# CPU.net
KiCad netlist of a schematic drawn in Altium Designer
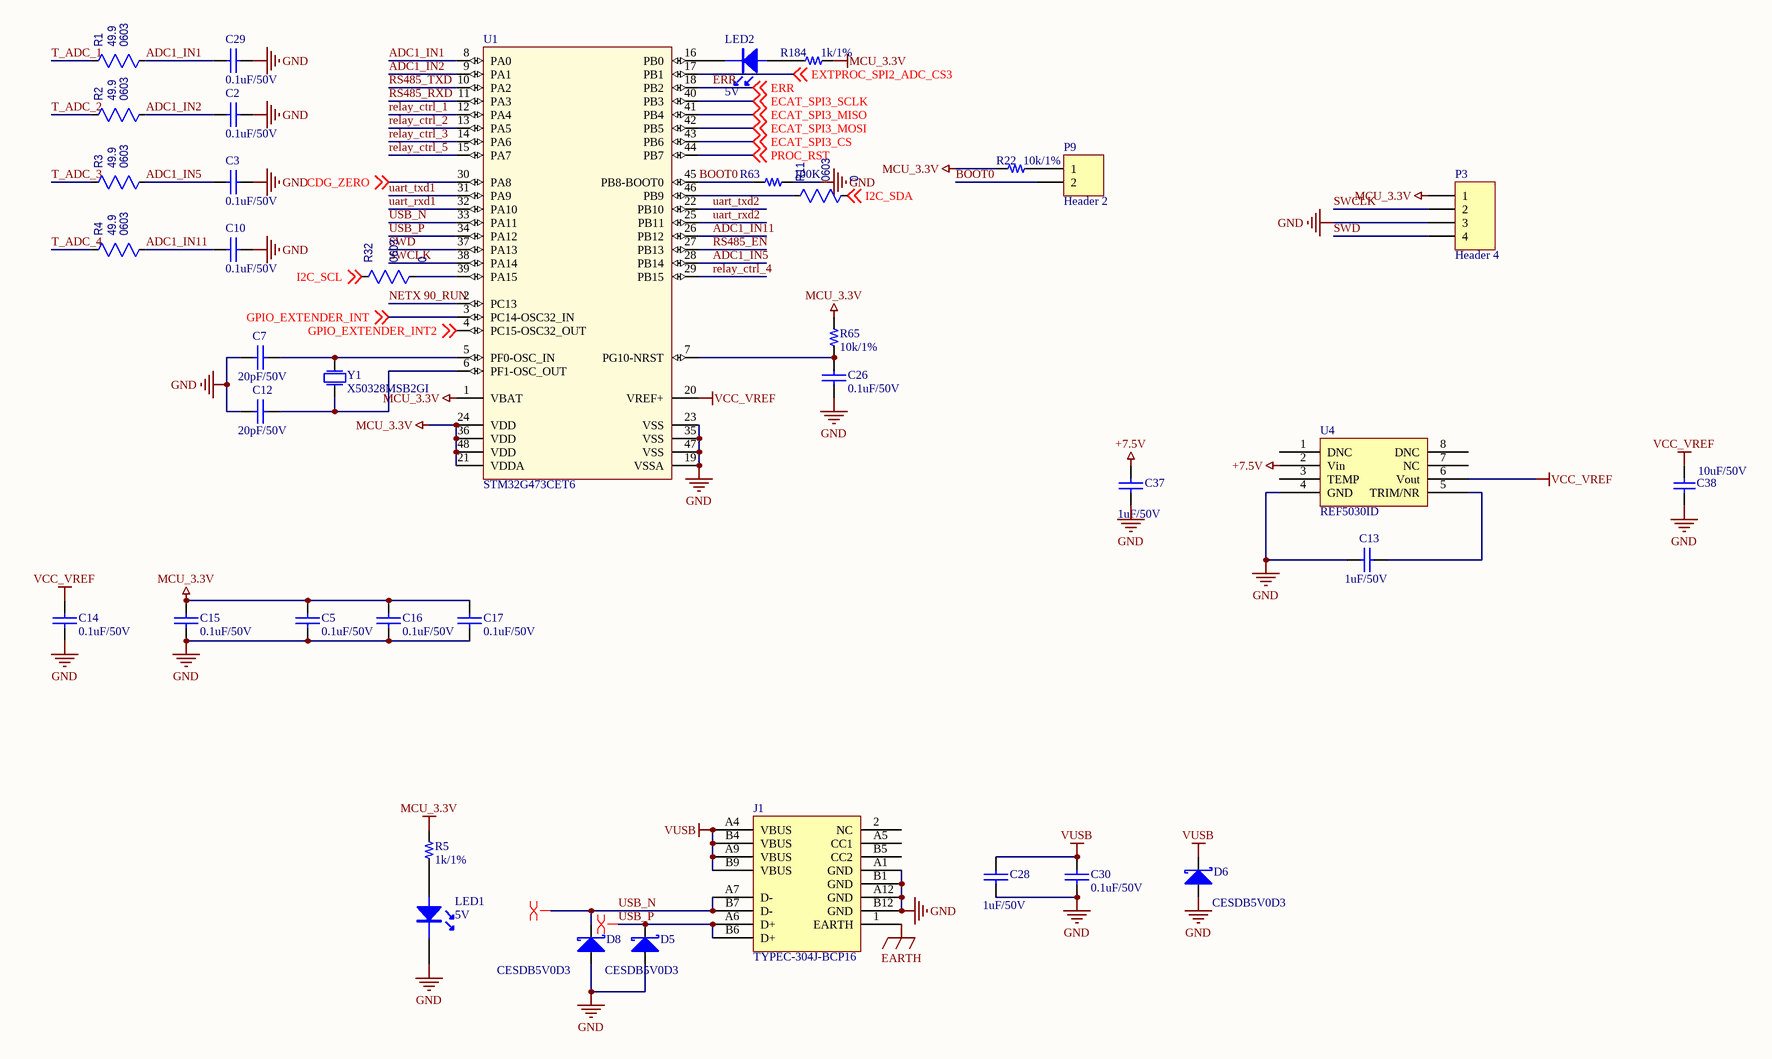
[diagram p0: CPU.SchDoc]

(export (version "E")
  (design (tool "Eeschema 10.0.6"))
  (components
    (comp (ref "C2")
      (value "0.1uF/50V")
      (footprint "CAPC1608X092N_0603")
      (fields (field (name "PARTNUMBER") "CC0603KRX7R9BB104"))
      (libsource (lib "SM") (part "CAP"))
    )
    (comp (ref "C3")
      (value "0.1uF/50V")
      (footprint "CAPC1608X092N_0603")
      (fields (field (name "PARTNUMBER") "CC0603KRX7R9BB104"))
      (libsource (lib "SM") (part "CAP"))
    )
    (comp (ref "C5")
      (value "0.1uF/50V")
      (footprint "CAPC1608X092N_0603")
      (fields (field (name "PARTNUMBER") "CC0603KRX7R9BB104"))
      (libsource (lib "SM") (part "CAP"))
    )
    (comp (ref "C7")
      (value "20pF/50V")
      (footprint "CAPC1608X092N_0603")
      (fields (field (name "PARTNUMBER") "CC0603JRNPO9BN200") (field (name "Comment") "20pF/25V"))
      (libsource (lib "SM") (part "CAP"))
    )
    (comp (ref "C10")
      (value "0.1uF/50V")
      (footprint "CAPC1608X092N_0603")
      (fields (field (name "PARTNUMBER") "CC0603KRX7R9BB104"))
      (libsource (lib "SM") (part "CAP"))
    )
    (comp (ref "C12")
      (value "20pF/50V")
      (footprint "CAPC1608X092N_0603")
      (fields (field (name "PARTNUMBER") "CC0603JRNPO9BN200") (field (name "Comment") "20pF/25V"))
      (libsource (lib "SM") (part "CAP"))
    )
    (comp (ref "C13")
      (value "1uF/50V")
      (footprint "CAPC1608X092N_0603")
      (fields (field (name "PARTNUMBER") "CL10A105KB8NNNC"))
      (libsource (lib "SM") (part "CAP"))
    )
    (comp (ref "C14")
      (value "0.1uF/50V")
      (footprint "CAPC1608X092N_0603")
      (fields (field (name "PARTNUMBER") "CC0603KRX7R9BB104"))
      (libsource (lib "SM") (part "CAP"))
    )
    (comp (ref "C15")
      (value "0.1uF/50V")
      (footprint "CAPC1608X092N_0603")
      (fields (field (name "PARTNUMBER") "CC0603KRX7R9BB104"))
      (libsource (lib "SM") (part "CAP"))
    )
    (comp (ref "C16")
      (value "0.1uF/50V")
      (footprint "CAPC1608X092N_0603")
      (fields (field (name "PARTNUMBER") "CC0603KRX7R9BB104"))
      (libsource (lib "SM") (part "CAP"))
    )
    (comp (ref "C17")
      (value "0.1uF/50V")
      (footprint "CAPC1608X092N_0603")
      (fields (field (name "PARTNUMBER") "CC0603KRX7R9BB104"))
      (libsource (lib "SM") (part "CAP"))
    )
    (comp (ref "C26")
      (value "0.1uF/50V")
      (footprint "CAPC1608X092N_0603")
      (fields (field (name "PARTNUMBER") "CC0603KRX7R9BB104"))
      (libsource (lib "SM") (part "CAP"))
    )
    (comp (ref "C28")
      (value "1uF/50V")
      (footprint "CAPC1608X092N_0603")
      (fields (field (name "PARTNUMBER") "CL10A105KB8NNNC"))
      (libsource (lib "SM") (part "CAP"))
    )
    (comp (ref "C29")
      (value "0.1uF/50V")
      (footprint "CAPC1608X092N_0603")
      (fields (field (name "PARTNUMBER") "CC0603KRX7R9BB104"))
      (libsource (lib "SM") (part "CAP"))
    )
    (comp (ref "C30")
      (value "0.1uF/50V")
      (footprint "CAPC1608X092N_0603")
      (fields (field (name "PARTNUMBER") "CC0603KRX7R9BB104"))
      (libsource (lib "SM") (part "CAP"))
    )
    (comp (ref "C37")
      (value "1uF/50V")
      (footprint "CAPC1608X092N_0603")
      (fields (field (name "PARTNUMBER") "CL10A105KB8NNNC"))
      (libsource (lib "SM") (part "CAP"))
    )
    (comp (ref "C38")
      (value "10uF/50V")
      (footprint "CAPC2012X127N_0805")
      (fields (field (name "PARTNUMBER") "CL21A106KBYQNNE") (field (name "PUBLISHER") "Altium Limited"))
      (libsource (lib "Miscellaneous Devices") (part "Cap"))
    )
    (comp (ref "D5") (value "CESDB5V0D3") (footprint "SOD323") (libsource (lib "*") (part "DIODE S")))
    (comp (ref "D6") (value "CESDB5V0D3") (footprint "SOD323") (libsource (lib "*") (part "DIODE S")))
    (comp (ref "D8") (value "CESDB5V0D3") (footprint "SOD323") (libsource (lib "*") (part "DIODE S")))
    (comp (ref "J1")
      (value "TYPEC-304J-BCP16")
      (footprint "TYPEC_16P")
      (libsource (lib "Schlib_20110825") (part "TYPE C_16P"))
    )
    (comp (ref "LED1") (value "5V") (footprint "0603LED") (libsource (lib "*") (part "LED")))
    (comp (ref "LED2") (value "5V") (footprint "0603LED") (libsource (lib "*") (part "LED")))
    (comp (ref "P3")
      (value "Header 4")
      (footprint "HDR1X4")
      (fields (field (name "PARTNUMBER") "PZ254V-11-04P") (field (name "PUBLISHER") "Altium Limited"))
      (libsource (lib "Miscellaneous Connectors") (part "Header 4"))
    )
    (comp (ref "P9")
      (value "Header 2")
      (footprint "HDR1X2")
      (fields (field (name "PARTNUMBER") "PZ254V-11-02P") (field (name "PUBLISHER") "Altium Limited"))
      (libsource (lib "Miscellaneous Connectors") (part "Header 2"))
    )
    (comp (ref "R1")
      (value "49.9")
      (footprint "RESC1608X055N_0603")
      (fields
        (field (name "PARTNUMBER") "RC0603FR-0749R9L")
        (field (name "TOLERANCE") "tol")
        (field (name "PACKAGE") "0603")
      )
      (libsource (lib "Karl") (part "Resistor_0603"))
    )
    (comp (ref "R2")
      (value "49.9")
      (footprint "RESC1608X055N_0603")
      (fields
        (field (name "PARTNUMBER") "RC0603FR-0749R9L")
        (field (name "TOLERANCE") "tol")
        (field (name "PACKAGE") "0603")
      )
      (libsource (lib "Karl") (part "Resistor_0603"))
    )
    (comp (ref "R3")
      (value "49.9")
      (footprint "RESC1608X055N_0603")
      (fields
        (field (name "PARTNUMBER") "RC0603FR-0749R9L")
        (field (name "TOLERANCE") "tol")
        (field (name "PACKAGE") "0603")
      )
      (libsource (lib "Karl") (part "Resistor_0603"))
    )
    (comp (ref "R4")
      (value "49.9")
      (footprint "RESC1608X055N_0603")
      (fields
        (field (name "PARTNUMBER") "RC0603FR-0749R9L")
        (field (name "TOLERANCE") "tol")
        (field (name "PACKAGE") "0603")
      )
      (libsource (lib "Karl") (part "Resistor_0603"))
    )
    (comp (ref "R5")
      (value "1k/1%")
      (footprint "RESC1608X055N_0603")
      (fields (field (name "PARTNUMBER") "RC0603FR-071KL"))
      (libsource (lib "JRJ_1") (part "R"))
    )
    (comp (ref "R11")
      (value "0")
      (footprint "RESC1608X055N_0603")
      (fields
        (field (name "PARTNUMBER") "RC0603JR-070RL")
        (field (name "TOLERANCE") "tol")
        (field (name "PACKAGE") "0603")
      )
      (libsource (lib "Karl") (part "Resistor_0603"))
    )
    (comp (ref "R22")
      (value "10k/1%")
      (footprint "RESC1608X055N_0603")
      (fields (field (name "PARTNUMBER") "RC0603FR-0710KL"))
      (libsource (lib "JRJ_1") (part "R"))
    )
    (comp (ref "R32")
      (value "0")
      (footprint "RESC1608X055N_0603")
      (fields
        (field (name "PARTNUMBER") "RC0603JR-070RL")
        (field (name "TOLERANCE") "tol")
        (field (name "PACKAGE") "0603")
      )
      (libsource (lib "Karl") (part "Resistor_0603"))
    )
    (comp (ref "R63")
      (value "100K")
      (footprint "RESC1608X055N_0603")
      (fields (field (name "PARTNUMBER") "RC0603FR-07100KL"))
      (libsource (lib "JRJ_1") (part "R"))
    )
    (comp (ref "R65")
      (value "10k/1%")
      (footprint "RESC1608X055N_0603")
      (fields (field (name "PARTNUMBER") "RC0603FR-0710KL"))
      (libsource (lib "JRJ_1") (part "R"))
    )
    (comp (ref "R184")
      (value "1k/1%")
      (footprint "RESC1608X055N_0603")
      (fields (field (name "PARTNUMBER") "RC0603FR-071KL"))
      (libsource (lib "JRJ_1") (part "R"))
    )
    (comp (ref "U1")
      (value "STM32G473CET6")
      (footprint "Bogen:STM-LQFP48_N")
      (libsource (lib "Bogen") (part "STM32G473CET6"))
    )
    (comp (ref "U4")
      (value "REF5030ID")
      (footprint "SO-8")
      (fields (field (name "PARTNUMBER") "REF5030IDR"))
      (libsource (lib "Schlib1") (part "REF5030"))
    )
    (comp (ref "Y1")
      (value "X50328MSB2GI")
      (footprint "CRAY_5032")
      (libsource (lib "Miscellaneous Devices") (part "XTAL"))
    )
  )
  (nets
    (net (code "1") (name "+7.5V") (class "Default")
      (node (ref "C37") (pin "2") (pinfunction "2_2") (pintype "passive"))
      (node (ref "U4") (pin "2") (pinfunction "Vin_2") (pintype "passive"))
    )
    (net (code "2") (name "/ADC1_IN1") (class "Default")
      (node (ref "C29") (pin "2") (pinfunction "2_2") (pintype "passive"))
      (node (ref "R1") (pin "1") (pinfunction "1_1") (pintype "passive"))
      (node (ref "U1") (pin "8") (pinfunction "PA0_8") (pintype "bidirectional"))
    )
    (net (code "3") (name "/ADC1_IN2") (class "Default")
      (node (ref "C2") (pin "2") (pinfunction "2_2") (pintype "passive"))
      (node (ref "R2") (pin "1") (pinfunction "1_1") (pintype "passive"))
      (node (ref "U1") (pin "9") (pinfunction "PA1_9") (pintype "bidirectional"))
    )
    (net (code "4") (name "/ADC1_IN5") (class "Default")
      (node (ref "C3") (pin "2") (pinfunction "2_2") (pintype "passive"))
      (node (ref "R3") (pin "1") (pinfunction "1_1") (pintype "passive"))
      (node (ref "U1") (pin "28") (pinfunction "PB14_28") (pintype "bidirectional"))
    )
    (net (code "5") (name "/ADC1_IN11") (class "Default")
      (node (ref "C10") (pin "2") (pinfunction "2_2") (pintype "passive"))
      (node (ref "R4") (pin "1") (pinfunction "1_1") (pintype "passive"))
      (node (ref "U1") (pin "26") (pinfunction "PB12_26") (pintype "bidirectional"))
    )
    (net (code "6") (name "/BOOT0") (class "Default")
      (node (ref "P9") (pin "2") (pinfunction "2_2") (pintype "passive"))
      (node (ref "R63") (pin "1") (pintype "passive"))
      (node (ref "U1") (pin "45") (pinfunction "PB8-BOOT0_45") (pintype "bidirectional"))
    )
    (net (code "7") (name "/NETX 90_RUN") (class "Default")
      (node (ref "U1") (pin "2") (pinfunction "PC13_2") (pintype "bidirectional"))
    )
    (net (code "8") (name "/RS485_EN") (class "Default")
      (node (ref "U1") (pin "27") (pinfunction "PB13_27") (pintype "bidirectional"))
    )
    (net (code "9") (name "/RS485_RXD") (class "Default")
      (node (ref "U1") (pin "11") (pinfunction "PA3_11") (pintype "bidirectional"))
    )
    (net (code "10") (name "/RS485_TXD") (class "Default")
      (node (ref "U1") (pin "10") (pinfunction "PA2_10") (pintype "bidirectional"))
    )
    (net (code "11") (name "/SWCLK") (class "Default")
      (node (ref "P3") (pin "2") (pinfunction "2_2") (pintype "passive"))
      (node (ref "U1") (pin "38") (pinfunction "PA14_38") (pintype "bidirectional"))
    )
    (net (code "12") (name "/SWD") (class "Default")
      (node (ref "P3") (pin "4") (pinfunction "4_4") (pintype "passive"))
      (node (ref "U1") (pin "37") (pinfunction "PA13_37") (pintype "bidirectional"))
    )
    (net (code "13") (name "/T_ADC_1") (class "Default")
      (node (ref "R1") (pin "2") (pinfunction "2_2") (pintype "passive"))
    )
    (net (code "14") (name "/T_ADC_2") (class "Default")
      (node (ref "R2") (pin "2") (pinfunction "2_2") (pintype "passive"))
    )
    (net (code "15") (name "/T_ADC_3") (class "Default")
      (node (ref "R3") (pin "2") (pinfunction "2_2") (pintype "passive"))
    )
    (net (code "16") (name "/T_ADC_4") (class "Default")
      (node (ref "R4") (pin "2") (pinfunction "2_2") (pintype "passive"))
    )
    (net (code "17") (name "/USB_N") (class "Default")
      (node (ref "D8") (pin "2") (pinfunction "K_2") (pintype "passive"))
      (node (ref "J1") (pin "A7") (pinfunction "D-_A7") (pintype "passive"))
      (node (ref "J1") (pin "B7") (pinfunction "D-_B7") (pintype "passive"))
      (node (ref "U1") (pin "33") (pinfunction "PA11_33") (pintype "bidirectional"))
    )
    (net (code "18") (name "/USB_P") (class "Default")
      (node (ref "D5") (pin "2") (pinfunction "K_2") (pintype "passive"))
      (node (ref "J1") (pin "A6") (pinfunction "D+_A6") (pintype "passive"))
      (node (ref "J1") (pin "B6") (pinfunction "D+_B6") (pintype "passive"))
      (node (ref "U1") (pin "34") (pinfunction "PA12_34") (pintype "bidirectional"))
    )
    (net (code "19") (name "/relay_ctrl_1") (class "Default")
      (node (ref "U1") (pin "12") (pinfunction "PA4_12") (pintype "bidirectional"))
    )
    (net (code "20") (name "/relay_ctrl_2") (class "Default")
      (node (ref "U1") (pin "13") (pinfunction "PA5_13") (pintype "bidirectional"))
    )
    (net (code "21") (name "/relay_ctrl_3") (class "Default")
      (node (ref "U1") (pin "14") (pinfunction "PA6_14") (pintype "bidirectional"))
    )
    (net (code "22") (name "/relay_ctrl_4") (class "Default")
      (node (ref "U1") (pin "29") (pinfunction "PB15_29") (pintype "bidirectional"))
    )
    (net (code "23") (name "/relay_ctrl_5") (class "Default")
      (node (ref "U1") (pin "15") (pinfunction "PA7_15") (pintype "bidirectional"))
    )
    (net (code "24") (name "/uart_rxd1") (class "Default")
      (node (ref "U1") (pin "32") (pinfunction "PA10_32") (pintype "bidirectional"))
    )
    (net (code "25") (name "/uart_rxd2") (class "Default")
      (node (ref "U1") (pin "25") (pinfunction "PB11_25") (pintype "bidirectional"))
    )
    (net (code "26") (name "/uart_txd1") (class "Default")
      (node (ref "U1") (pin "31") (pinfunction "PA9_31") (pintype "bidirectional"))
    )
    (net (code "27") (name "/uart_txd2") (class "Default")
      (node (ref "U1") (pin "22") (pinfunction "PB10_22") (pintype "bidirectional"))
    )
    (net (code "28") (name "CDG_ZERO") (class "Default")
      (node (ref "U1") (pin "30") (pinfunction "PA8_30") (pintype "bidirectional"))
    )
    (net (code "29") (name "EARTH") (class "Default")
      (node (ref "J1") (pin "1") (pinfunction "EARTH_1") (pintype "passive"))
    )
    (net (code "30") (name "ECAT_SPI3_CS") (class "Default")
      (node (ref "U1") (pin "43") (pinfunction "PB6_43") (pintype "bidirectional"))
    )
    (net (code "31") (name "ECAT_SPI3_MISO") (class "Default")
      (node (ref "U1") (pin "41") (pinfunction "PB4_41") (pintype "bidirectional"))
    )
    (net (code "32") (name "ECAT_SPI3_MOSI") (class "Default")
      (node (ref "U1") (pin "42") (pinfunction "PB5_42") (pintype "bidirectional"))
    )
    (net (code "33") (name "ECAT_SPI3_SCLK") (class "Default")
      (node (ref "U1") (pin "40") (pinfunction "PB3_40") (pintype "bidirectional"))
    )
    (net (code "34") (name "ERR") (class "Default")
      (node (ref "U1") (pin "18") (pinfunction "PB2_18") (pintype "bidirectional"))
    )
    (net (code "35") (name "EXTPROC_SPI2_ADC_CS3") (class "Default")
      (node (ref "U1") (pin "17") (pinfunction "PB1_17") (pintype "bidirectional"))
    )
    (net (code "36") (name "GND") (class "Default")
      (node (ref "C10") (pin "1") (pinfunction "1_1") (pintype "passive"))
      (node (ref "C12") (pin "2") (pinfunction "2_2") (pintype "passive"))
      (node (ref "C13") (pin "2") (pinfunction "2_2") (pintype "passive"))
      (node (ref "C14") (pin "1") (pinfunction "1_1") (pintype "passive"))
      (node (ref "C15") (pin "1") (pinfunction "1_1") (pintype "passive"))
      (node (ref "C16") (pin "1") (pinfunction "1_1") (pintype "passive"))
      (node (ref "C17") (pin "1") (pinfunction "1_1") (pintype "passive"))
      (node (ref "C2") (pin "1") (pinfunction "1_1") (pintype "passive"))
      (node (ref "C26") (pin "1") (pinfunction "1_1") (pintype "passive"))
      (node (ref "C28") (pin "1") (pinfunction "1_1") (pintype "passive"))
      (node (ref "C29") (pin "1") (pinfunction "1_1") (pintype "passive"))
      (node (ref "C3") (pin "1") (pinfunction "1_1") (pintype "passive"))
      (node (ref "C30") (pin "1") (pinfunction "1_1") (pintype "passive"))
      (node (ref "C37") (pin "1") (pinfunction "1_1") (pintype "passive"))
      (node (ref "C38") (pin "1") (pinfunction "1_1") (pintype "passive"))
      (node (ref "C5") (pin "1") (pinfunction "1_1") (pintype "passive"))
      (node (ref "C7") (pin "2") (pinfunction "2_2") (pintype "passive"))
      (node (ref "D5") (pin "1") (pinfunction "A_1") (pintype "passive"))
      (node (ref "D6") (pin "1") (pinfunction "A_1") (pintype "passive"))
      (node (ref "D8") (pin "1") (pinfunction "A_1") (pintype "passive"))
      (node (ref "J1") (pin "A1") (pinfunction "GND_A1") (pintype "passive"))
      (node (ref "J1") (pin "A12") (pinfunction "GND_A12") (pintype "passive"))
      (node (ref "J1") (pin "B1") (pinfunction "GND_B1") (pintype "passive"))
      (node (ref "J1") (pin "B12") (pinfunction "GND_B12") (pintype "passive"))
      (node (ref "LED1") (pin "2") (pinfunction "2_2") (pintype "passive"))
      (node (ref "P3") (pin "3") (pinfunction "3_3") (pintype "passive"))
      (node (ref "R63") (pin "2") (pintype "passive"))
      (node (ref "U1") (pin "19") (pinfunction "VSSA_19") (pintype "power_in"))
      (node (ref "U1") (pin "23") (pinfunction "VSS_23") (pintype "power_in"))
      (node (ref "U1") (pin "35") (pinfunction "VSS_35") (pintype "power_in"))
      (node (ref "U1") (pin "47") (pinfunction "VSS_47") (pintype "power_in"))
      (node (ref "U4") (pin "4") (pinfunction "GND_4") (pintype "passive"))
    )
    (net (code "37") (name "GPIO_EXTENDER_INT") (class "Default")
      (node (ref "U1") (pin "3") (pinfunction "PC14-OSC32_IN_3") (pintype "bidirectional"))
    )
    (net (code "38") (name "GPIO_EXTENDER_INT2") (class "Default")
      (node (ref "U1") (pin "4") (pinfunction "PC15-OSC32_OUT_4") (pintype "bidirectional"))
    )
    (net (code "39") (name "I2C_SCL") (class "Default")
      (node (ref "R32") (pin "2") (pinfunction "2_2") (pintype "passive"))
    )
    (net (code "40") (name "I2C_SDA") (class "Default")
      (node (ref "R11") (pin "1") (pinfunction "1_1") (pintype "passive"))
    )
    (net (code "41") (name "MCU_3.3V") (class "Default")
      (node (ref "C15") (pin "2") (pinfunction "2_2") (pintype "passive"))
      (node (ref "C16") (pin "2") (pinfunction "2_2") (pintype "passive"))
      (node (ref "C17") (pin "2") (pinfunction "2_2") (pintype "passive"))
      (node (ref "C5") (pin "2") (pinfunction "2_2") (pintype "passive"))
      (node (ref "P3") (pin "1") (pinfunction "1_1") (pintype "passive"))
      (node (ref "R184") (pin "2") (pintype "passive"))
      (node (ref "R22") (pin "1") (pintype "passive"))
      (node (ref "R5") (pin "2") (pintype "passive"))
      (node (ref "R65") (pin "1") (pintype "passive"))
      (node (ref "U1") (pin "1") (pinfunction "VBAT_1") (pintype "power_in"))
      (node (ref "U1") (pin "21") (pinfunction "VDDA_21") (pintype "power_in"))
      (node (ref "U1") (pin "24") (pinfunction "VDD_24") (pintype "power_in"))
      (node (ref "U1") (pin "36") (pinfunction "VDD_36") (pintype "power_in"))
      (node (ref "U1") (pin "48") (pinfunction "VDD_48") (pintype "power_in"))
    )
    (net (code "42") (name "Net-(LED1-Pad1)") (class "Default")
      (node (ref "LED1") (pin "1") (pinfunction "1_1") (pintype "passive"))
      (node (ref "R5") (pin "1") (pintype "passive"))
    )
    (net (code "43") (name "Net-(LED2-Pad1)") (class "Default")
      (node (ref "LED2") (pin "1") (pinfunction "1_1") (pintype "passive"))
      (node (ref "R184") (pin "1") (pintype "passive"))
    )
    (net (code "44") (name "Net-(P9-Pad1)") (class "Default")
      (node (ref "P9") (pin "1") (pinfunction "1_1") (pintype "passive"))
      (node (ref "R22") (pin "2") (pintype "passive"))
    )
    (net (code "45") (name "Net-(U1-PA15)") (class "Default")
      (node (ref "R32") (pin "1") (pinfunction "1_1") (pintype "passive"))
      (node (ref "U1") (pin "39") (pinfunction "PA15_39") (pintype "bidirectional"))
    )
    (net (code "46") (name "Net-(U1-PB0)") (class "Default")
      (node (ref "LED2") (pin "2") (pinfunction "2_2") (pintype "passive"))
      (node (ref "U1") (pin "16") (pinfunction "PB0_16") (pintype "bidirectional"))
    )
    (net (code "47") (name "Net-(U1-PB9)") (class "Default")
      (node (ref "R11") (pin "2") (pinfunction "2_2") (pintype "passive"))
      (node (ref "U1") (pin "46") (pinfunction "PB9_46") (pintype "bidirectional"))
    )
    (net (code "48") (name "Net-(U1-PF0-OSC_IN)") (class "Default")
      (node (ref "C7") (pin "1") (pinfunction "1_1") (pintype "passive"))
      (node (ref "U1") (pin "5") (pinfunction "PF0-OSC_IN_5") (pintype "bidirectional"))
      (node (ref "Y1") (pin "1") (pinfunction "P1_1") (pintype "passive"))
    )
    (net (code "49") (name "Net-(U1-PF1-OSC_OUT)") (class "Default")
      (node (ref "C12") (pin "1") (pinfunction "1_1") (pintype "passive"))
      (node (ref "U1") (pin "6") (pinfunction "PF1-OSC_OUT_6") (pintype "bidirectional"))
      (node (ref "Y1") (pin "2") (pinfunction "P2_2") (pintype "passive"))
    )
    (net (code "50") (name "Net-(U1-PG10-NRST)") (class "Default")
      (node (ref "C26") (pin "2") (pinfunction "2_2") (pintype "passive"))
      (node (ref "R65") (pin "2") (pintype "passive"))
      (node (ref "U1") (pin "7") (pinfunction "PG10-NRST_7") (pintype "bidirectional"))
    )
    (net (code "51") (name "Net-(U4-TRIM{slash}NR)") (class "Default")
      (node (ref "C13") (pin "1") (pinfunction "1_1") (pintype "passive"))
      (node (ref "U4") (pin "5") (pinfunction "TRIM/NR_5") (pintype "passive"))
    )
    (net (code "52") (name "PROC_RST") (class "Default")
      (node (ref "U1") (pin "44") (pinfunction "PB7_44") (pintype "bidirectional"))
    )
    (net (code "53") (name "VCC_VREF") (class "Default")
      (node (ref "C14") (pin "2") (pinfunction "2_2") (pintype "passive"))
      (node (ref "C38") (pin "2") (pinfunction "2_2") (pintype "passive"))
      (node (ref "U1") (pin "20") (pinfunction "VREF+_20") (pintype "power_in"))
      (node (ref "U4") (pin "6") (pinfunction "Vout_6") (pintype "passive"))
    )
    (net (code "54") (name "VUSB") (class "Default")
      (node (ref "C28") (pin "2") (pinfunction "2_2") (pintype "passive"))
      (node (ref "C30") (pin "2") (pinfunction "2_2") (pintype "passive"))
      (node (ref "D6") (pin "2") (pinfunction "K_2") (pintype "passive"))
      (node (ref "J1") (pin "A4") (pinfunction "VBUS_A4") (pintype "passive"))
      (node (ref "J1") (pin "A9") (pinfunction "VBUS_A9") (pintype "passive"))
      (node (ref "J1") (pin "B4") (pinfunction "VBUS_B4") (pintype "passive"))
      (node (ref "J1") (pin "B9") (pinfunction "VBUS_B9") (pintype "passive"))
    )
    (net (code "55") (name "unconnected-(J1-CC1-PadA5)") (class "Default")
      (node (ref "J1") (pin "A5") (pinfunction "CC1_A5") (pintype "passive"))
    )
    (net (code "56") (name "unconnected-(J1-CC2-PadB5)") (class "Default")
      (node (ref "J1") (pin "B5") (pinfunction "CC2_B5") (pintype "passive"))
    )
    (net (code "57") (name "unconnected-(J1-NC-Pad2)") (class "Default")
      (node (ref "J1") (pin "2") (pinfunction "NC_2") (pintype "passive"))
    )
    (net (code "58") (name "unconnected-(U4-DNC-Pad1)") (class "Default")
      (node (ref "U4") (pin "1") (pinfunction "DNC_1") (pintype "passive"))
    )
    (net (code "59") (name "unconnected-(U4-DNC-Pad8)") (class "Default")
      (node (ref "U4") (pin "8") (pinfunction "DNC_8") (pintype "passive"))
    )
    (net (code "60") (name "unconnected-(U4-NC-Pad7)") (class "Default")
      (node (ref "U4") (pin "7") (pinfunction "NC_7") (pintype "passive"))
    )
    (net (code "61") (name "unconnected-(U4-TEMP-Pad3)") (class "Default")
      (node (ref "U4") (pin "3") (pinfunction "TEMP_3") (pintype "passive"))
    )
  )
)
